# Sheet3.net
KiCad netlist of a schematic drawn in Altium Designer
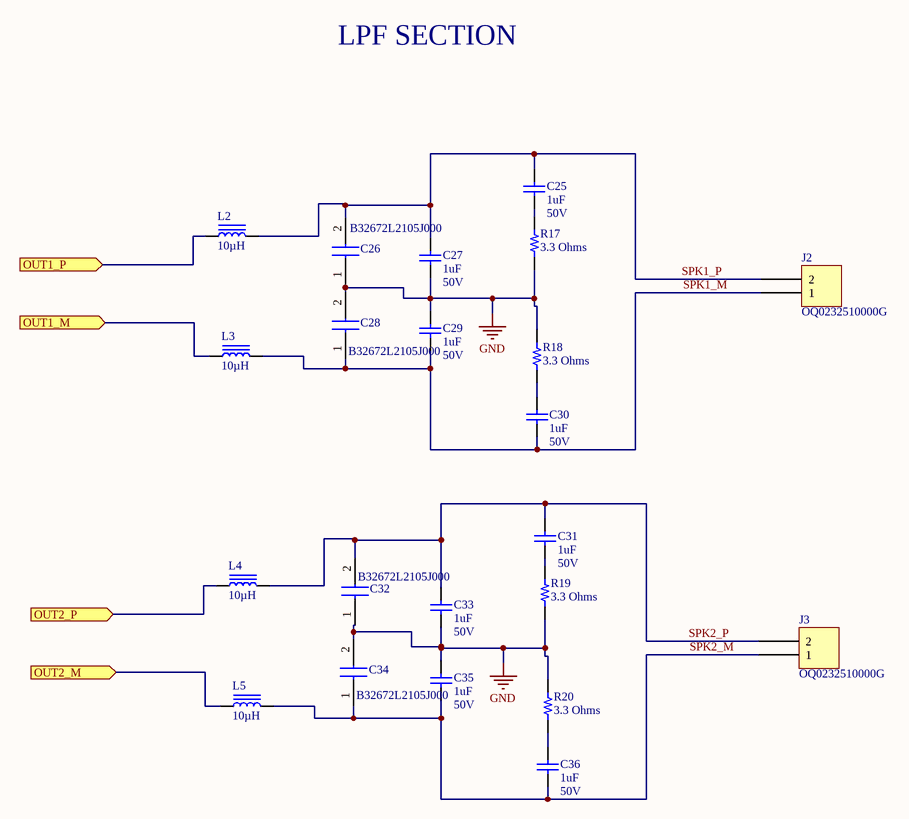
[diagram p0: Sheet3.SchDoc]

(export (version "E")
  (design (tool "Eeschema 10.0.6"))
  (components
    (comp (ref "C25")
      (value "1uF")
      (footprint "C0805")
      (description "CAP 1uF 10% 50V X7R 0805")
      (fields (field (name "VRATING") "50V"))
      (libsource (lib "Database_Libs1") (part "CAP_NPOL"))
    )
    (comp (ref "C26")
      (value "B32672L2105J000")
      (footprint "SamacSys:B32672L2105J000")
      (description "Capacitor")
      (fields (field (name "MOUSER PART NUMBER") "871-B32672L2105J000"))
      (libsource (lib "*") (part "B32672L2105J000"))
    )
    (comp (ref "C27")
      (value "1uF")
      (footprint "C0805")
      (description "CAP 1uF 10% 50V X7R 0805")
      (fields (field (name "VRATING") "50V"))
      (libsource (lib "Database_Libs1") (part "CAP_NPOL"))
    )
    (comp (ref "C28")
      (value "B32672L2105J000")
      (footprint "SamacSys:B32672L2105J000")
      (description "Capacitor")
      (fields (field (name "MOUSER PART NUMBER") "871-B32672L2105J000"))
      (libsource (lib "*") (part "B32672L2105J000"))
    )
    (comp (ref "C29")
      (value "1uF")
      (footprint "C0805")
      (description "CAP 1uF 10% 50V X7R 0805")
      (fields (field (name "VRATING") "50V"))
      (libsource (lib "Database_Libs1") (part "CAP_NPOL"))
    )
    (comp (ref "C30")
      (value "1uF")
      (footprint "C0805")
      (description "CAP 1uF 10% 50V X7R 0805")
      (fields (field (name "VRATING") "50V"))
      (libsource (lib "Database_Libs1") (part "CAP_NPOL"))
    )
    (comp (ref "C31")
      (value "1uF")
      (footprint "C0805")
      (description "CAP 1uF 10% 50V X7R 0805")
      (fields (field (name "VRATING") "50V"))
      (libsource (lib "Database_Libs1") (part "CAP_NPOL"))
    )
    (comp (ref "C32")
      (value "B32672L2105J000")
      (footprint "SamacSys:B32672L2105J000")
      (description "Capacitor")
      (fields (field (name "MOUSER PART NUMBER") "871-B32672L2105J000"))
      (libsource (lib "*") (part "B32672L2105J000"))
    )
    (comp (ref "C33")
      (value "1uF")
      (footprint "C0805")
      (description "CAP 1uF 10% 50V X7R 0805")
      (fields (field (name "VRATING") "50V"))
      (libsource (lib "Database_Libs1") (part "CAP_NPOL"))
    )
    (comp (ref "C34")
      (value "B32672L2105J000")
      (footprint "SamacSys:B32672L2105J000")
      (description "Capacitor")
      (fields (field (name "MOUSER PART NUMBER") "871-B32672L2105J000"))
      (libsource (lib "*") (part "B32672L2105J000"))
    )
    (comp (ref "C35")
      (value "1uF")
      (footprint "C0805")
      (description "CAP 1uF 10% 50V X7R 0805")
      (fields (field (name "VRATING") "50V"))
      (libsource (lib "Database_Libs1") (part "CAP_NPOL"))
    )
    (comp (ref "C36")
      (value "1uF")
      (footprint "C0805")
      (description "CAP 1uF 10% 50V X7R 0805")
      (fields (field (name "VRATING") "50V"))
      (libsource (lib "Database_Libs1") (part "CAP_NPOL"))
    )
    (comp (ref "J2")
      (value "OQ0232510000G")
      (footprint "FCI 06-381-2PIN")
      (description "TERM BLOCK HDR 2POS 90DEG 3.81MM")
      (fields (field (name "MANUFACTURER") "Amphenol Anytek"))
      (libsource (lib "Celestial Altium Library - altium_library") (part "2 Pin"))
    )
    (comp (ref "J3")
      (value "OQ0232510000G")
      (footprint "FCI 06-381-2PIN")
      (description "TERM BLOCK HDR 2POS 90DEG 3.81MM")
      (fields (field (name "MANUFACTURER") "Amphenol Anytek"))
      (libsource (lib "Celestial Altium Library - altium_library") (part "2 Pin"))
    )
    (comp (ref "L2")
      (value "10µH")
      (footprint "TDK SLF12575")
      (description "FIXED IND 10UH 5.4A 15.6 MOHM")
      (fields
        (field (name "PART NUMBER") "SLF12575T-100M5R4-PF")
        (field (name "MANUFACTURER") "TDK Corporation")
      )
      (libsource (lib "Celestial Altium Library - altium_library") (part "Inductor"))
    )
    (comp (ref "L3")
      (value "10µH")
      (footprint "TDK SLF12575")
      (description "FIXED IND 10UH 5.4A 15.6 MOHM")
      (fields
        (field (name "PART NUMBER") "SLF12575T-100M5R4-PF")
        (field (name "MANUFACTURER") "TDK Corporation")
      )
      (libsource (lib "Celestial Altium Library - altium_library") (part "Inductor"))
    )
    (comp (ref "L4")
      (value "10µH")
      (footprint "TDK SLF12575")
      (description "FIXED IND 10UH 5.4A 15.6 MOHM")
      (fields
        (field (name "PART NUMBER") "SLF12575T-100M5R4-PF")
        (field (name "MANUFACTURER") "TDK Corporation")
      )
      (libsource (lib "Celestial Altium Library - altium_library") (part "Inductor"))
    )
    (comp (ref "L5")
      (value "10µH")
      (footprint "TDK SLF12575")
      (description "FIXED IND 10UH 5.4A 15.6 MOHM")
      (fields
        (field (name "PART NUMBER") "SLF12575T-100M5R4-PF")
        (field (name "MANUFACTURER") "TDK Corporation")
      )
      (libsource (lib "Celestial Altium Library - altium_library") (part "Inductor"))
    )
    (comp (ref "R17")
      (value "3.3 Ohms")
      (footprint "RES 0805_2012")
      (description "RES SMD 3.3 OHM 1% 1/2W 0805")
      (fields (field (name "PART NUMBER") "CRCW08053R30FKEAHP") (field (name "MANUFACTURER") "Vishay Dale"))
      (libsource (lib "Celestial Altium Library - altium_library") (part "Resistor"))
    )
    (comp (ref "R18")
      (value "3.3 Ohms")
      (footprint "RES 0805_2012")
      (description "RES SMD 3.3 OHM 1% 1/2W 0805")
      (fields (field (name "PART NUMBER") "CRCW08053R30FKEAHP") (field (name "MANUFACTURER") "Vishay Dale"))
      (libsource (lib "Celestial Altium Library - altium_library") (part "Resistor"))
    )
    (comp (ref "R19")
      (value "3.3 Ohms")
      (footprint "RES 0805_2012")
      (description "RES SMD 3.3 OHM 1% 1/2W 0805")
      (fields (field (name "PART NUMBER") "CRCW08053R30FKEAHP") (field (name "MANUFACTURER") "Vishay Dale"))
      (libsource (lib "Celestial Altium Library - altium_library") (part "Resistor"))
    )
    (comp (ref "R20")
      (value "3.3 Ohms")
      (footprint "RES 0805_2012")
      (description "RES SMD 3.3 OHM 1% 1/2W 0805")
      (fields (field (name "PART NUMBER") "CRCW08053R30FKEAHP") (field (name "MANUFACTURER") "Vishay Dale"))
      (libsource (lib "Celestial Altium Library - altium_library") (part "Resistor"))
    )
  )
  (nets
    (net (code "1") (name "/OUT1_M") (class "Default")
      (node (ref "L3") (pin "1") (pinfunction "1_1") (pintype "passive"))
    )
    (net (code "2") (name "/OUT1_P") (class "Default")
      (node (ref "L2") (pin "1") (pinfunction "1_1") (pintype "passive"))
    )
    (net (code "3") (name "/OUT2_M") (class "Default")
      (node (ref "L5") (pin "1") (pinfunction "1_1") (pintype "passive"))
    )
    (net (code "4") (name "/OUT2_P") (class "Default")
      (node (ref "L4") (pin "1") (pinfunction "1_1") (pintype "passive"))
    )
    (net (code "5") (name "/SPK1_M") (class "Default")
      (node (ref "C28") (pin "1") (pinfunction "1_1") (pintype "passive"))
      (node (ref "C29") (pin "1") (pinfunction "1_1") (pintype "passive"))
      (node (ref "C30") (pin "1") (pinfunction "1_1") (pintype "passive"))
      (node (ref "J2") (pin "1") (pinfunction "1_1") (pintype "passive"))
      (node (ref "L3") (pin "2") (pinfunction "2_2") (pintype "passive"))
    )
    (net (code "6") (name "/SPK1_P") (class "Default")
      (node (ref "C25") (pin "2") (pinfunction "2_2") (pintype "passive"))
      (node (ref "C26") (pin "2") (pinfunction "2_2") (pintype "passive"))
      (node (ref "C27") (pin "2") (pinfunction "2_2") (pintype "passive"))
      (node (ref "J2") (pin "2") (pinfunction "2_2") (pintype "passive"))
      (node (ref "L2") (pin "2") (pinfunction "2_2") (pintype "passive"))
    )
    (net (code "7") (name "/SPK2_M") (class "Default")
      (node (ref "C34") (pin "1") (pinfunction "1_1") (pintype "passive"))
      (node (ref "C35") (pin "1") (pinfunction "1_1") (pintype "passive"))
      (node (ref "C36") (pin "1") (pinfunction "1_1") (pintype "passive"))
      (node (ref "J3") (pin "1") (pinfunction "1_1") (pintype "passive"))
      (node (ref "L5") (pin "2") (pinfunction "2_2") (pintype "passive"))
    )
    (net (code "8") (name "/SPK2_P") (class "Default")
      (node (ref "C31") (pin "2") (pinfunction "2_2") (pintype "passive"))
      (node (ref "C32") (pin "2") (pinfunction "2_2") (pintype "passive"))
      (node (ref "C33") (pin "2") (pinfunction "2_2") (pintype "passive"))
      (node (ref "J3") (pin "2") (pinfunction "2_2") (pintype "passive"))
      (node (ref "L4") (pin "2") (pinfunction "2_2") (pintype "passive"))
    )
    (net (code "9") (name "GND") (class "Default")
      (node (ref "C26") (pin "1") (pinfunction "1_1") (pintype "passive"))
      (node (ref "C27") (pin "1") (pinfunction "1_1") (pintype "passive"))
      (node (ref "C28") (pin "2") (pinfunction "2_2") (pintype "passive"))
      (node (ref "C29") (pin "2") (pinfunction "2_2") (pintype "passive"))
      (node (ref "C32") (pin "1") (pinfunction "1_1") (pintype "passive"))
      (node (ref "C33") (pin "1") (pinfunction "1_1") (pintype "passive"))
      (node (ref "C34") (pin "2") (pinfunction "2_2") (pintype "passive"))
      (node (ref "C35") (pin "2") (pinfunction "2_2") (pintype "passive"))
      (node (ref "R17") (pin "1") (pinfunction "1_1") (pintype "passive"))
      (node (ref "R18") (pin "2") (pinfunction "2_2") (pintype "passive"))
      (node (ref "R19") (pin "1") (pinfunction "1_1") (pintype "passive"))
      (node (ref "R20") (pin "2") (pinfunction "2_2") (pintype "passive"))
    )
    (net (code "10") (name "Net-(C25-Pad1)") (class "Default")
      (node (ref "C25") (pin "1") (pinfunction "1_1") (pintype "passive"))
      (node (ref "R17") (pin "2") (pinfunction "2_2") (pintype "passive"))
    )
    (net (code "11") (name "Net-(C30-Pad2)") (class "Default")
      (node (ref "C30") (pin "2") (pinfunction "2_2") (pintype "passive"))
      (node (ref "R18") (pin "1") (pinfunction "1_1") (pintype "passive"))
    )
    (net (code "12") (name "Net-(C31-Pad1)") (class "Default")
      (node (ref "C31") (pin "1") (pinfunction "1_1") (pintype "passive"))
      (node (ref "R19") (pin "2") (pinfunction "2_2") (pintype "passive"))
    )
    (net (code "13") (name "Net-(C36-Pad2)") (class "Default")
      (node (ref "C36") (pin "2") (pinfunction "2_2") (pintype "passive"))
      (node (ref "R20") (pin "1") (pinfunction "1_1") (pintype "passive"))
    )
  )
)
